# 5HP_Datalogger.net
KiCad netlist of a schematic drawn in EAGLE
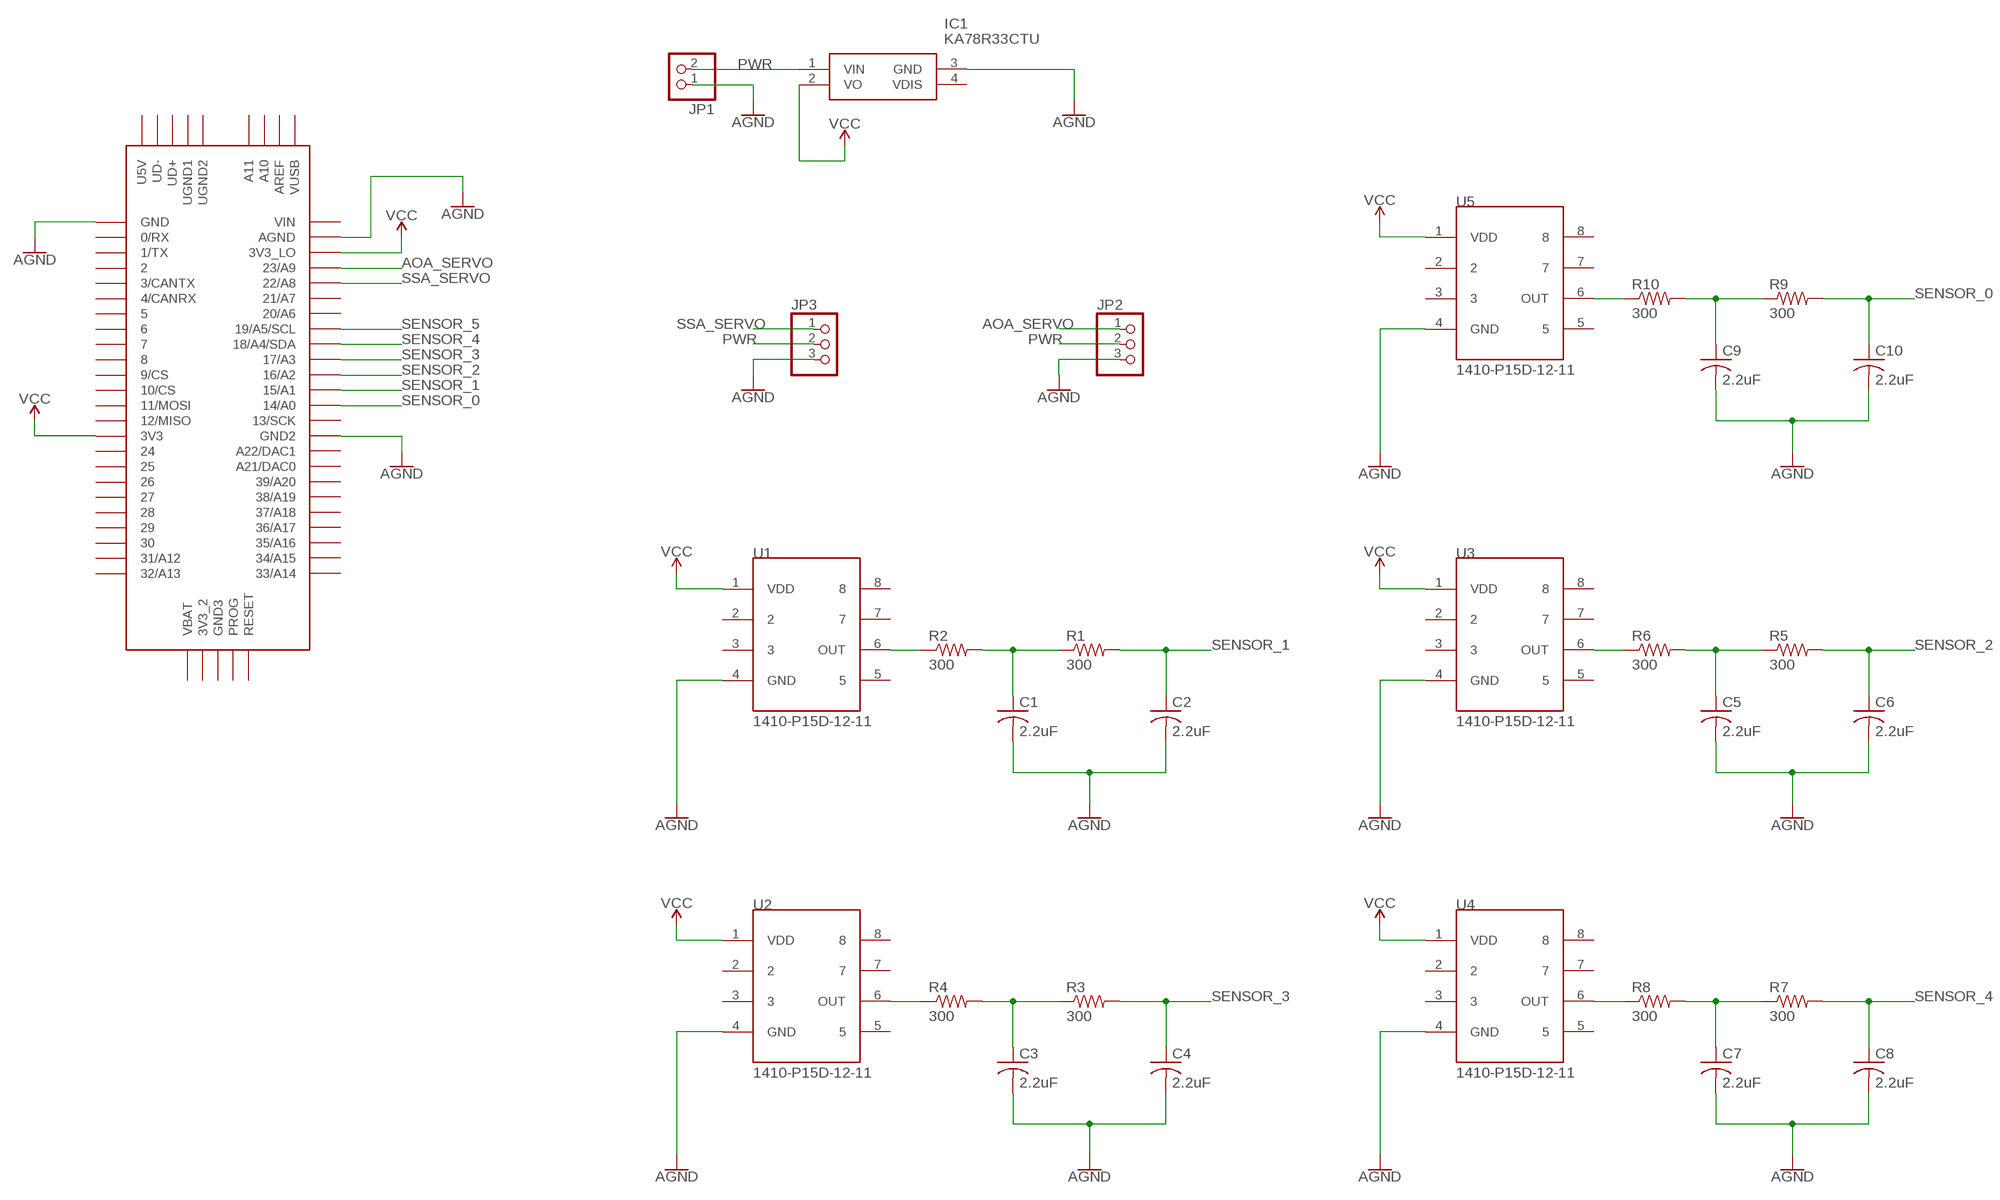
[diagram p0: schematic, sheet 1]

(export (version "E")
  (design (tool "Eeschema 10.0.6"))
  (components
    (comp (ref "C1")
      (value "2.2uF")
      (footprint "eagle-import:C075-032X103")
      (libsource (lib "eagle-import") (part "C-US075-032X103"))
    )
    (comp (ref "C2")
      (value "2.2uF")
      (footprint "eagle-import:C075-032X103")
      (libsource (lib "eagle-import") (part "C-US075-032X103"))
    )
    (comp (ref "C3")
      (value "2.2uF")
      (footprint "eagle-import:C075-032X103")
      (libsource (lib "eagle-import") (part "C-US075-032X103"))
    )
    (comp (ref "C4")
      (value "2.2uF")
      (footprint "eagle-import:C075-032X103")
      (libsource (lib "eagle-import") (part "C-US075-032X103"))
    )
    (comp (ref "C5")
      (value "2.2uF")
      (footprint "eagle-import:C075-032X103")
      (libsource (lib "eagle-import") (part "C-US075-032X103"))
    )
    (comp (ref "C6")
      (value "2.2uF")
      (footprint "eagle-import:C075-032X103")
      (libsource (lib "eagle-import") (part "C-US075-032X103"))
    )
    (comp (ref "C7")
      (value "2.2uF")
      (footprint "eagle-import:C075-032X103")
      (libsource (lib "eagle-import") (part "C-US075-032X103"))
    )
    (comp (ref "C8")
      (value "2.2uF")
      (footprint "eagle-import:C075-032X103")
      (libsource (lib "eagle-import") (part "C-US075-032X103"))
    )
    (comp (ref "C9")
      (value "2.2uF")
      (footprint "eagle-import:C075-032X103")
      (libsource (lib "eagle-import") (part "C-US075-032X103"))
    )
    (comp (ref "C10")
      (value "2.2uF")
      (footprint "eagle-import:C075-032X103")
      (libsource (lib "eagle-import") (part "C-US075-032X103"))
    )
    (comp (ref "IC1")
      (value "KA78R33CTU")
      (footprint "eagle-import:TO254P470X1000X1960-4P")
      (fields (field (name "RS_PART_NUMBER") "8064368"))
      (libsource (lib "eagle-import") (part "KA78R33CTU"))
    )
    (comp (ref "JP1")
      (value "PINHD-1X2")
      (footprint "eagle-import:1X02")
      (libsource (lib "eagle-import") (part "PINHD-1X2"))
    )
    (comp (ref "JP2")
      (value "PINHD-1X3")
      (footprint "eagle-import:1X03")
      (libsource (lib "eagle-import") (part "PINHD-1X3"))
    )
    (comp (ref "JP3")
      (value "PINHD-1X3")
      (footprint "eagle-import:1X03")
      (libsource (lib "eagle-import") (part "PINHD-1X3"))
    )
    (comp (ref "R1")
      (value "300")
      (footprint "eagle-import:0207_10")
      (libsource (lib "eagle-import") (part "R-US_0207/10"))
    )
    (comp (ref "R2")
      (value "300")
      (footprint "eagle-import:0207_10")
      (libsource (lib "eagle-import") (part "R-US_0207/10"))
    )
    (comp (ref "R3")
      (value "300")
      (footprint "eagle-import:0207_10")
      (libsource (lib "eagle-import") (part "R-US_0207/10"))
    )
    (comp (ref "R4")
      (value "300")
      (footprint "eagle-import:0207_10")
      (libsource (lib "eagle-import") (part "R-US_0207/10"))
    )
    (comp (ref "R5")
      (value "300")
      (footprint "eagle-import:0207_10")
      (libsource (lib "eagle-import") (part "R-US_0207/10"))
    )
    (comp (ref "R6")
      (value "300")
      (footprint "eagle-import:0207_10")
      (libsource (lib "eagle-import") (part "R-US_0207/10"))
    )
    (comp (ref "R7")
      (value "300")
      (footprint "eagle-import:0207_10")
      (libsource (lib "eagle-import") (part "R-US_0207/10"))
    )
    (comp (ref "R8")
      (value "300")
      (footprint "eagle-import:0207_10")
      (libsource (lib "eagle-import") (part "R-US_0207/10"))
    )
    (comp (ref "R9")
      (value "300")
      (footprint "eagle-import:0207_10")
      (libsource (lib "eagle-import") (part "R-US_0207/10"))
    )
    (comp (ref "R10")
      (value "300")
      (footprint "eagle-import:0207_10")
      (libsource (lib "eagle-import") (part "R-US_0207/10"))
    )
    (comp (ref "U$2")
      (value "TEENSY_3.5/3.6")
      (footprint "eagle-import:TEENSY_3.5_3.6")
      (libsource (lib "eagle-import") (part "TEENSY_3.5/3.6"))
    )
    (comp (ref "U1")
      (value "1410-P15D-12-11")
      (footprint "eagle-import:1410-P15D-12-11")
      (libsource (lib "eagle-import") (part "1410-P15D-12-11"))
    )
    (comp (ref "U2")
      (value "1410-P15D-12-11")
      (footprint "eagle-import:1410-P15D-12-11")
      (libsource (lib "eagle-import") (part "1410-P15D-12-11"))
    )
    (comp (ref "U3")
      (value "1410-P15D-12-11")
      (footprint "eagle-import:1410-P15D-12-11")
      (libsource (lib "eagle-import") (part "1410-P15D-12-11"))
    )
    (comp (ref "U4")
      (value "1410-P15D-12-11")
      (footprint "eagle-import:1410-P15D-12-11")
      (libsource (lib "eagle-import") (part "1410-P15D-12-11"))
    )
    (comp (ref "U5")
      (value "1410-P15D-12-11")
      (footprint "eagle-import:1410-P15D-12-11")
      (libsource (lib "eagle-import") (part "1410-P15D-12-11"))
    )
  )
  (nets
    (net (code "1") (name "/AOA_SERVO") (class "Default")
      (node (ref "JP2") (pin "1") (pinfunction "1_1") (pintype "passive"))
      (node (ref "U$2") (pin "23/A9") (pinfunction "23/A9_23/A9") (pintype "bidirectional"))
    )
    (net (code "2") (name "/PWR") (class "Default")
      (node (ref "IC1") (pin "1") (pinfunction "VIN_1") (pintype "input"))
      (node (ref "JP1") (pin "2") (pinfunction "2_2") (pintype "passive"))
      (node (ref "JP2") (pin "2") (pinfunction "2_2") (pintype "passive"))
      (node (ref "JP3") (pin "2") (pinfunction "2_2") (pintype "passive"))
    )
    (net (code "3") (name "/SENSOR_0") (class "Default")
      (node (ref "C10") (pin "1") (pinfunction "1_1") (pintype "passive"))
      (node (ref "R9") (pin "2") (pinfunction "2_2") (pintype "passive"))
      (node (ref "U$2") (pin "14/A0") (pinfunction "14/A0_14/A0") (pintype "bidirectional"))
    )
    (net (code "4") (name "/SENSOR_1") (class "Default")
      (node (ref "C2") (pin "1") (pinfunction "1_1") (pintype "passive"))
      (node (ref "R1") (pin "2") (pinfunction "2_2") (pintype "passive"))
      (node (ref "U$2") (pin "15/A1") (pinfunction "15/A1_15/A1") (pintype "bidirectional"))
    )
    (net (code "5") (name "/SENSOR_2") (class "Default")
      (node (ref "C6") (pin "1") (pinfunction "1_1") (pintype "passive"))
      (node (ref "R5") (pin "2") (pinfunction "2_2") (pintype "passive"))
      (node (ref "U$2") (pin "16/A2") (pinfunction "16/A2_16/A2") (pintype "bidirectional"))
    )
    (net (code "6") (name "/SENSOR_3") (class "Default")
      (node (ref "C4") (pin "1") (pinfunction "1_1") (pintype "passive"))
      (node (ref "R3") (pin "2") (pinfunction "2_2") (pintype "passive"))
      (node (ref "U$2") (pin "17/A3") (pinfunction "17/A3_17/A3") (pintype "bidirectional"))
    )
    (net (code "7") (name "/SENSOR_4") (class "Default")
      (node (ref "C8") (pin "1") (pinfunction "1_1") (pintype "passive"))
      (node (ref "R7") (pin "2") (pinfunction "2_2") (pintype "passive"))
      (node (ref "U$2") (pin "18/A4/SDA") (pinfunction "18/A4/SDA_18/A4/SDA") (pintype "bidirectional"))
    )
    (net (code "8") (name "/SENSOR_5") (class "Default")
      (node (ref "U$2") (pin "19/A5/SCL") (pinfunction "19/A5/SCL_19/A5/SCL") (pintype "bidirectional"))
    )
    (net (code "9") (name "/SSA_SERVO") (class "Default")
      (node (ref "JP3") (pin "1") (pinfunction "1_1") (pintype "passive"))
      (node (ref "U$2") (pin "22/A8") (pinfunction "22/A8_22/A8") (pintype "bidirectional"))
    )
    (net (code "10") (name "AGND") (class "Default")
      (node (ref "C1") (pin "2") (pinfunction "2_2") (pintype "passive"))
      (node (ref "C10") (pin "2") (pinfunction "2_2") (pintype "passive"))
      (node (ref "C2") (pin "2") (pinfunction "2_2") (pintype "passive"))
      (node (ref "C3") (pin "2") (pinfunction "2_2") (pintype "passive"))
      (node (ref "C4") (pin "2") (pinfunction "2_2") (pintype "passive"))
      (node (ref "C5") (pin "2") (pinfunction "2_2") (pintype "passive"))
      (node (ref "C6") (pin "2") (pinfunction "2_2") (pintype "passive"))
      (node (ref "C7") (pin "2") (pinfunction "2_2") (pintype "passive"))
      (node (ref "C8") (pin "2") (pinfunction "2_2") (pintype "passive"))
      (node (ref "C9") (pin "2") (pinfunction "2_2") (pintype "passive"))
      (node (ref "IC1") (pin "3") (pinfunction "GND_3") (pintype "power_in"))
      (node (ref "JP1") (pin "1") (pinfunction "1_1") (pintype "passive"))
      (node (ref "JP2") (pin "3") (pinfunction "3_3") (pintype "passive"))
      (node (ref "JP3") (pin "3") (pinfunction "3_3") (pintype "passive"))
      (node (ref "U$2") (pin "AGND") (pinfunction "AGND_AGND") (pintype "bidirectional"))
      (node (ref "U$2") (pin "GND") (pinfunction "GND_GND") (pintype "bidirectional"))
      (node (ref "U$2") (pin "GND2") (pinfunction "GND2_GND2") (pintype "bidirectional"))
      (node (ref "U1") (pin "4") (pinfunction "GND_4") (pintype "power_in"))
      (node (ref "U2") (pin "4") (pinfunction "GND_4") (pintype "power_in"))
      (node (ref "U3") (pin "4") (pinfunction "GND_4") (pintype "power_in"))
      (node (ref "U4") (pin "4") (pinfunction "GND_4") (pintype "power_in"))
      (node (ref "U5") (pin "4") (pinfunction "GND_4") (pintype "power_in"))
    )
    (net (code "11") (name "Net-(C1-Pad1)") (class "Default")
      (node (ref "C1") (pin "1") (pinfunction "1_1") (pintype "passive"))
      (node (ref "R1") (pin "1") (pinfunction "1_1") (pintype "passive"))
      (node (ref "R2") (pin "2") (pinfunction "2_2") (pintype "passive"))
    )
    (net (code "12") (name "Net-(C3-Pad1)") (class "Default")
      (node (ref "C3") (pin "1") (pinfunction "1_1") (pintype "passive"))
      (node (ref "R3") (pin "1") (pinfunction "1_1") (pintype "passive"))
      (node (ref "R4") (pin "2") (pinfunction "2_2") (pintype "passive"))
    )
    (net (code "13") (name "Net-(C5-Pad1)") (class "Default")
      (node (ref "C5") (pin "1") (pinfunction "1_1") (pintype "passive"))
      (node (ref "R5") (pin "1") (pinfunction "1_1") (pintype "passive"))
      (node (ref "R6") (pin "2") (pinfunction "2_2") (pintype "passive"))
    )
    (net (code "14") (name "Net-(C7-Pad1)") (class "Default")
      (node (ref "C7") (pin "1") (pinfunction "1_1") (pintype "passive"))
      (node (ref "R7") (pin "1") (pinfunction "1_1") (pintype "passive"))
      (node (ref "R8") (pin "2") (pinfunction "2_2") (pintype "passive"))
    )
    (net (code "15") (name "Net-(C9-Pad1)") (class "Default")
      (node (ref "C9") (pin "1") (pinfunction "1_1") (pintype "passive"))
      (node (ref "R10") (pin "2") (pinfunction "2_2") (pintype "passive"))
      (node (ref "R9") (pin "1") (pinfunction "1_1") (pintype "passive"))
    )
    (net (code "16") (name "Net-(U1-OUT)") (class "Default")
      (node (ref "R2") (pin "1") (pinfunction "1_1") (pintype "passive"))
      (node (ref "U1") (pin "6") (pinfunction "OUT_6") (pintype "output"))
    )
    (net (code "17") (name "Net-(U2-OUT)") (class "Default")
      (node (ref "R4") (pin "1") (pinfunction "1_1") (pintype "passive"))
      (node (ref "U2") (pin "6") (pinfunction "OUT_6") (pintype "output"))
    )
    (net (code "18") (name "Net-(U3-OUT)") (class "Default")
      (node (ref "R6") (pin "1") (pinfunction "1_1") (pintype "passive"))
      (node (ref "U3") (pin "6") (pinfunction "OUT_6") (pintype "output"))
    )
    (net (code "19") (name "Net-(U4-OUT)") (class "Default")
      (node (ref "R8") (pin "1") (pinfunction "1_1") (pintype "passive"))
      (node (ref "U4") (pin "6") (pinfunction "OUT_6") (pintype "output"))
    )
    (net (code "20") (name "Net-(U5-OUT)") (class "Default")
      (node (ref "R10") (pin "1") (pinfunction "1_1") (pintype "passive"))
      (node (ref "U5") (pin "6") (pinfunction "OUT_6") (pintype "output"))
    )
    (net (code "21") (name "VCC") (class "Default")
      (node (ref "IC1") (pin "2") (pinfunction "VO_2") (pintype "bidirectional"))
      (node (ref "U$2") (pin "3V3") (pinfunction "3V3_3V3") (pintype "bidirectional"))
      (node (ref "U$2") (pin "3V3_LO") (pinfunction "3V3_LO_3V3_LO") (pintype "bidirectional"))
      (node (ref "U1") (pin "1") (pinfunction "VDD_1") (pintype "power_in"))
      (node (ref "U2") (pin "1") (pinfunction "VDD_1") (pintype "power_in"))
      (node (ref "U3") (pin "1") (pinfunction "VDD_1") (pintype "power_in"))
      (node (ref "U4") (pin "1") (pinfunction "VDD_1") (pintype "power_in"))
      (node (ref "U5") (pin "1") (pinfunction "VDD_1") (pintype "power_in"))
    )
    (net (code "22") (name "unconnected-(IC1-VDIS-Pad4)") (class "Default")
      (node (ref "IC1") (pin "4") (pinfunction "VDIS_4") (pintype "bidirectional"))
    )
    (net (code "23") (name "unconnected-(U$2-A21{slash}DAC0-Pad21{slash}DAC0)") (class "Default")
      (node (ref "U$2") (pin "21/DAC0") (pinfunction "A21/DAC0_21/DAC0") (pintype "bidirectional"))
    )
    (net (code "24") (name "unconnected-(U$2-Pad0{slash}RX)") (class "Default")
      (node (ref "U$2") (pin "0/RX") (pinfunction "0/RX_0/RX") (pintype "bidirectional"))
    )
    (net (code "25") (name "unconnected-(U$2-Pad1{slash}TX)") (class "Default")
      (node (ref "U$2") (pin "1/TX") (pinfunction "1/TX_1/TX") (pintype "bidirectional"))
    )
    (net (code "26") (name "unconnected-(U$2-Pad2)") (class "Default")
      (node (ref "U$2") (pin "2") (pinfunction "2_2") (pintype "bidirectional"))
    )
    (net (code "27") (name "unconnected-(U$2-Pad3V3_2)") (class "Default")
      (node (ref "U$2") (pin "3V3_2") (pinfunction "3V3_2_3V3_2") (pintype "bidirectional"))
    )
    (net (code "28") (name "unconnected-(U$2-Pad3{slash}CANTX)") (class "Default")
      (node (ref "U$2") (pin "3/CANTX") (pinfunction "3/CANTX_3/CANTX") (pintype "bidirectional"))
    )
    (net (code "29") (name "unconnected-(U$2-Pad4{slash}CANRX)") (class "Default")
      (node (ref "U$2") (pin "4/CANRX") (pinfunction "4/CANRX_4/CANRX") (pintype "bidirectional"))
    )
    (net (code "30") (name "unconnected-(U$2-Pad5)") (class "Default")
      (node (ref "U$2") (pin "5") (pinfunction "5_5") (pintype "bidirectional"))
    )
    (net (code "31") (name "unconnected-(U$2-Pad6)") (class "Default")
      (node (ref "U$2") (pin "6") (pinfunction "6_6") (pintype "bidirectional"))
    )
    (net (code "32") (name "unconnected-(U$2-Pad7)") (class "Default")
      (node (ref "U$2") (pin "7") (pinfunction "7_7") (pintype "bidirectional"))
    )
    (net (code "33") (name "unconnected-(U$2-Pad8)") (class "Default")
      (node (ref "U$2") (pin "8") (pinfunction "8_8") (pintype "bidirectional"))
    )
    (net (code "34") (name "unconnected-(U$2-Pad9{slash}CS)") (class "Default")
      (node (ref "U$2") (pin "9/CS") (pinfunction "9/CS_9/CS") (pintype "bidirectional"))
    )
    (net (code "35") (name "unconnected-(U$2-Pad10{slash}CS)") (class "Default")
      (node (ref "U$2") (pin "10/CS") (pinfunction "10/CS_10/CS") (pintype "bidirectional"))
    )
    (net (code "36") (name "unconnected-(U$2-Pad11{slash}MOSI)") (class "Default")
      (node (ref "U$2") (pin "11/MOSI") (pinfunction "11/MOSI_11/MOSI") (pintype "bidirectional"))
    )
    (net (code "37") (name "unconnected-(U$2-Pad12{slash}MISO)") (class "Default")
      (node (ref "U$2") (pin "12/MISO") (pinfunction "12/MISO_12/MISO") (pintype "bidirectional"))
    )
    (net (code "38") (name "unconnected-(U$2-Pad13{slash}SCK)") (class "Default")
      (node (ref "U$2") (pin "13/SCK") (pinfunction "13/SCK_13/SCK") (pintype "bidirectional"))
    )
    (net (code "39") (name "unconnected-(U$2-Pad20{slash}A6)") (class "Default")
      (node (ref "U$2") (pin "20/A6") (pinfunction "20/A6_20/A6") (pintype "bidirectional"))
    )
    (net (code "40") (name "unconnected-(U$2-Pad21{slash}A7)") (class "Default")
      (node (ref "U$2") (pin "21/A7") (pinfunction "21/A7_21/A7") (pintype "bidirectional"))
    )
    (net (code "41") (name "unconnected-(U$2-Pad24)") (class "Default")
      (node (ref "U$2") (pin "24") (pinfunction "24_24") (pintype "bidirectional"))
    )
    (net (code "42") (name "unconnected-(U$2-Pad25)") (class "Default")
      (node (ref "U$2") (pin "25") (pinfunction "25_25") (pintype "bidirectional"))
    )
    (net (code "43") (name "unconnected-(U$2-Pad26)") (class "Default")
      (node (ref "U$2") (pin "26") (pinfunction "26_26") (pintype "bidirectional"))
    )
    (net (code "44") (name "unconnected-(U$2-Pad27)") (class "Default")
      (node (ref "U$2") (pin "27") (pinfunction "27_27") (pintype "bidirectional"))
    )
    (net (code "45") (name "unconnected-(U$2-Pad28)") (class "Default")
      (node (ref "U$2") (pin "28") (pinfunction "28_28") (pintype "bidirectional"))
    )
    (net (code "46") (name "unconnected-(U$2-Pad29)") (class "Default")
      (node (ref "U$2") (pin "29") (pinfunction "29_29") (pintype "bidirectional"))
    )
    (net (code "47") (name "unconnected-(U$2-Pad30)") (class "Default")
      (node (ref "U$2") (pin "30") (pinfunction "30_30") (pintype "bidirectional"))
    )
    (net (code "48") (name "unconnected-(U$2-Pad31{slash}A12)") (class "Default")
      (node (ref "U$2") (pin "31/A12") (pinfunction "31/A12_31/A12") (pintype "bidirectional"))
    )
    (net (code "49") (name "unconnected-(U$2-Pad32{slash}A13)") (class "Default")
      (node (ref "U$2") (pin "32/A13") (pinfunction "32/A13_32/A13") (pintype "bidirectional"))
    )
    (net (code "50") (name "unconnected-(U$2-Pad33{slash}A14)") (class "Default")
      (node (ref "U$2") (pin "33/A14") (pinfunction "33/A14_33/A14") (pintype "bidirectional"))
    )
    (net (code "51") (name "unconnected-(U$2-Pad34{slash}A15)") (class "Default")
      (node (ref "U$2") (pin "34/A15") (pinfunction "34/A15_34/A15") (pintype "bidirectional"))
    )
    (net (code "52") (name "unconnected-(U$2-Pad35{slash}A16)") (class "Default")
      (node (ref "U$2") (pin "35/A16") (pinfunction "35/A16_35/A16") (pintype "bidirectional"))
    )
    (net (code "53") (name "unconnected-(U$2-Pad36{slash}A17)") (class "Default")
      (node (ref "U$2") (pin "36/A17") (pinfunction "36/A17_36/A17") (pintype "bidirectional"))
    )
    (net (code "54") (name "unconnected-(U$2-Pad37{slash}A18)") (class "Default")
      (node (ref "U$2") (pin "37/A18") (pinfunction "37/A18_37/A18") (pintype "bidirectional"))
    )
    (net (code "55") (name "unconnected-(U$2-Pad38{slash}A19)") (class "Default")
      (node (ref "U$2") (pin "38/A19") (pinfunction "38/A19_38/A19") (pintype "bidirectional"))
    )
    (net (code "56") (name "unconnected-(U$2-Pad39{slash}A20)") (class "Default")
      (node (ref "U$2") (pin "39/A20") (pinfunction "39/A20_39/A20") (pintype "bidirectional"))
    )
    (net (code "57") (name "unconnected-(U$2-PadA10)") (class "Default")
      (node (ref "U$2") (pin "A10") (pinfunction "A10_A10") (pintype "bidirectional"))
    )
    (net (code "58") (name "unconnected-(U$2-PadA11)") (class "Default")
      (node (ref "U$2") (pin "A11") (pinfunction "A11_A11") (pintype "bidirectional"))
    )
    (net (code "59") (name "unconnected-(U$2-PadA22{slash}DAC1)") (class "Default")
      (node (ref "U$2") (pin "A22/DAC1") (pinfunction "A22/DAC1_A22/DAC1") (pintype "bidirectional"))
    )
    (net (code "60") (name "unconnected-(U$2-PadAREF)") (class "Default")
      (node (ref "U$2") (pin "AREF") (pinfunction "AREF_AREF") (pintype "bidirectional"))
    )
    (net (code "61") (name "unconnected-(U$2-PadGND3)") (class "Default")
      (node (ref "U$2") (pin "GND3") (pinfunction "GND3_GND3") (pintype "bidirectional"))
    )
    (net (code "62") (name "unconnected-(U$2-PadPROG)") (class "Default")
      (node (ref "U$2") (pin "PROG") (pinfunction "PROG_PROG") (pintype "bidirectional"))
    )
    (net (code "63") (name "unconnected-(U$2-PadRESET)") (class "Default")
      (node (ref "U$2") (pin "RESET") (pinfunction "RESET_RESET") (pintype "bidirectional"))
    )
    (net (code "64") (name "unconnected-(U$2-PadU5V)") (class "Default")
      (node (ref "U$2") (pin "U5V") (pinfunction "U5V_U5V") (pintype "bidirectional"))
    )
    (net (code "65") (name "unconnected-(U$2-PadUD+)") (class "Default")
      (node (ref "U$2") (pin "UD+") (pinfunction "UD+_UD+") (pintype "bidirectional"))
    )
    (net (code "66") (name "unconnected-(U$2-PadUD-)") (class "Default")
      (node (ref "U$2") (pin "UD-") (pinfunction "UD-_UD-") (pintype "bidirectional"))
    )
    (net (code "67") (name "unconnected-(U$2-PadUGND1)") (class "Default")
      (node (ref "U$2") (pin "UGND1") (pinfunction "UGND1_UGND1") (pintype "bidirectional"))
    )
    (net (code "68") (name "unconnected-(U$2-PadUGND2)") (class "Default")
      (node (ref "U$2") (pin "UGND2") (pinfunction "UGND2_UGND2") (pintype "bidirectional"))
    )
    (net (code "69") (name "unconnected-(U$2-PadVBAT)") (class "Default")
      (node (ref "U$2") (pin "VBAT") (pinfunction "VBAT_VBAT") (pintype "bidirectional"))
    )
    (net (code "70") (name "unconnected-(U$2-PadVIN)") (class "Default")
      (node (ref "U$2") (pin "VIN") (pinfunction "VIN_VIN") (pintype "bidirectional"))
    )
    (net (code "71") (name "unconnected-(U$2-PadVUSB)") (class "Default")
      (node (ref "U$2") (pin "VUSB") (pinfunction "VUSB_VUSB") (pintype "bidirectional"))
    )
    (net (code "72") (name "unconnected-(U1-Pad2)") (class "Default")
      (node (ref "U1") (pin "2") (pinfunction "2_2") (pintype "no_connect"))
    )
    (net (code "73") (name "unconnected-(U1-Pad3)") (class "Default")
      (node (ref "U1") (pin "3") (pinfunction "3_3") (pintype "no_connect"))
    )
    (net (code "74") (name "unconnected-(U1-Pad5)") (class "Default")
      (node (ref "U1") (pin "5") (pinfunction "5_5") (pintype "no_connect"))
    )
    (net (code "75") (name "unconnected-(U1-Pad7)") (class "Default")
      (node (ref "U1") (pin "7") (pinfunction "7_7") (pintype "no_connect"))
    )
    (net (code "76") (name "unconnected-(U1-Pad8)") (class "Default")
      (node (ref "U1") (pin "8") (pinfunction "8_8") (pintype "no_connect"))
    )
    (net (code "77") (name "unconnected-(U2-Pad2)") (class "Default")
      (node (ref "U2") (pin "2") (pinfunction "2_2") (pintype "no_connect"))
    )
    (net (code "78") (name "unconnected-(U2-Pad3)") (class "Default")
      (node (ref "U2") (pin "3") (pinfunction "3_3") (pintype "no_connect"))
    )
    (net (code "79") (name "unconnected-(U2-Pad5)") (class "Default")
      (node (ref "U2") (pin "5") (pinfunction "5_5") (pintype "no_connect"))
    )
    (net (code "80") (name "unconnected-(U2-Pad7)") (class "Default")
      (node (ref "U2") (pin "7") (pinfunction "7_7") (pintype "no_connect"))
    )
    (net (code "81") (name "unconnected-(U2-Pad8)") (class "Default")
      (node (ref "U2") (pin "8") (pinfunction "8_8") (pintype "no_connect"))
    )
    (net (code "82") (name "unconnected-(U3-Pad2)") (class "Default")
      (node (ref "U3") (pin "2") (pinfunction "2_2") (pintype "no_connect"))
    )
    (net (code "83") (name "unconnected-(U3-Pad3)") (class "Default")
      (node (ref "U3") (pin "3") (pinfunction "3_3") (pintype "no_connect"))
    )
    (net (code "84") (name "unconnected-(U3-Pad5)") (class "Default")
      (node (ref "U3") (pin "5") (pinfunction "5_5") (pintype "no_connect"))
    )
    (net (code "85") (name "unconnected-(U3-Pad7)") (class "Default")
      (node (ref "U3") (pin "7") (pinfunction "7_7") (pintype "no_connect"))
    )
    (net (code "86") (name "unconnected-(U3-Pad8)") (class "Default")
      (node (ref "U3") (pin "8") (pinfunction "8_8") (pintype "no_connect"))
    )
    (net (code "87") (name "unconnected-(U4-Pad2)") (class "Default")
      (node (ref "U4") (pin "2") (pinfunction "2_2") (pintype "no_connect"))
    )
    (net (code "88") (name "unconnected-(U4-Pad3)") (class "Default")
      (node (ref "U4") (pin "3") (pinfunction "3_3") (pintype "no_connect"))
    )
    (net (code "89") (name "unconnected-(U4-Pad5)") (class "Default")
      (node (ref "U4") (pin "5") (pinfunction "5_5") (pintype "no_connect"))
    )
    (net (code "90") (name "unconnected-(U4-Pad7)") (class "Default")
      (node (ref "U4") (pin "7") (pinfunction "7_7") (pintype "no_connect"))
    )
    (net (code "91") (name "unconnected-(U4-Pad8)") (class "Default")
      (node (ref "U4") (pin "8") (pinfunction "8_8") (pintype "no_connect"))
    )
    (net (code "92") (name "unconnected-(U5-Pad2)") (class "Default")
      (node (ref "U5") (pin "2") (pinfunction "2_2") (pintype "no_connect"))
    )
    (net (code "93") (name "unconnected-(U5-Pad3)") (class "Default")
      (node (ref "U5") (pin "3") (pinfunction "3_3") (pintype "no_connect"))
    )
    (net (code "94") (name "unconnected-(U5-Pad5)") (class "Default")
      (node (ref "U5") (pin "5") (pinfunction "5_5") (pintype "no_connect"))
    )
    (net (code "95") (name "unconnected-(U5-Pad7)") (class "Default")
      (node (ref "U5") (pin "7") (pinfunction "7_7") (pintype "no_connect"))
    )
    (net (code "96") (name "unconnected-(U5-Pad8)") (class "Default")
      (node (ref "U5") (pin "8") (pinfunction "8_8") (pintype "no_connect"))
    )
  )
)
